# PlacaE3.net
KiCad netlist of a schematic drawn in Altium Designer
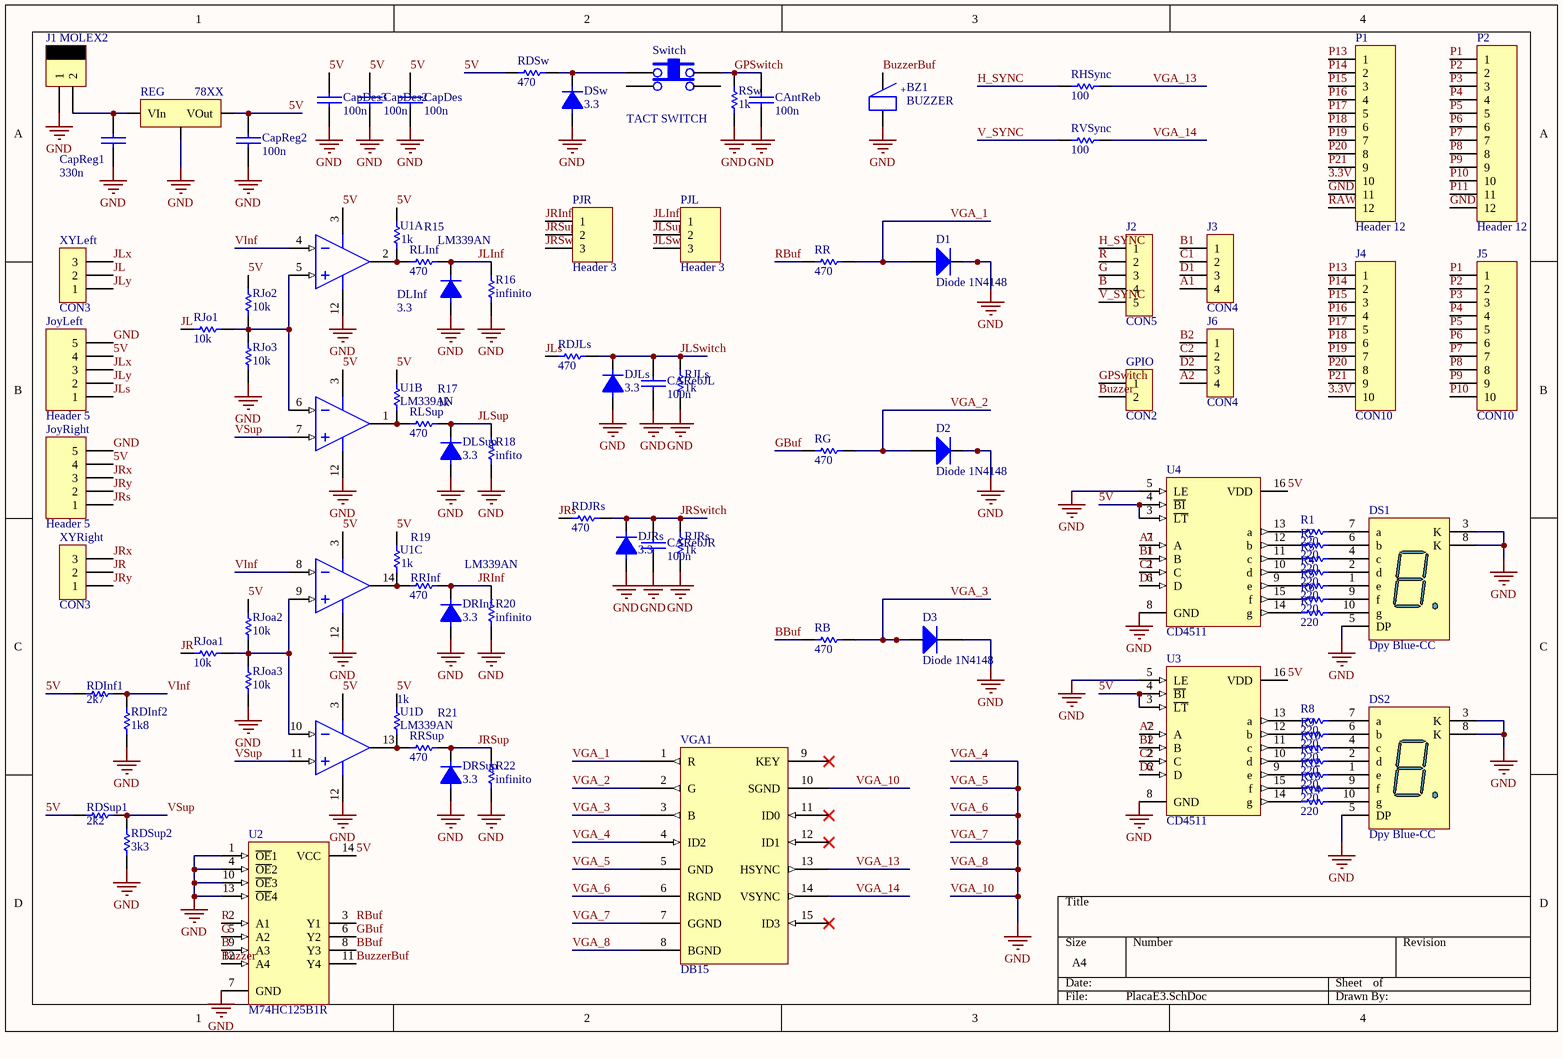
[diagram p0: PlacaE3.SchDoc]

(export (version "E")
  (design (tool "Eeschema 10.0.6"))
  (components
    (comp (ref "BZ1") (value "BUZZER") (footprint "BUZZER 12MM") (libsource (lib "LIBEBAL") (part "BUZZER")))
    (comp (ref "CAntReb") (value "100n") (footprint "CAP200") (libsource (lib "LIBEBAL") (part "CAP")))
    (comp (ref "CapDes") (value "100n") (footprint "CAP200") (libsource (lib "LIBEBAL") (part "CAP")))
    (comp (ref "CapDes2") (value "100n") (footprint "CAP200") (libsource (lib "LIBEBAL") (part "CAP")))
    (comp (ref "CapDes3") (value "100n") (footprint "CAP200") (libsource (lib "LIBEBAL") (part "CAP")))
    (comp (ref "CapReg1") (value "330n") (footprint "CAP200") (libsource (lib "LIBEBAL") (part "CAP")))
    (comp (ref "CapReg2") (value "100n") (footprint "CAP200") (libsource (lib "LIBEBAL") (part "CAP")))
    (comp (ref "CARebJL") (value "100n") (footprint "CAP200") (libsource (lib "LIBEBAL") (part "CAP")))
    (comp (ref "CARebJR") (value "100n") (footprint "CAP200") (libsource (lib "LIBEBAL") (part "CAP")))
    (comp (ref "D1")
      (value "Diode 1N4148")
      (footprint "DO-35")
      (description "High Conductance Fast Diode")
      (fields (field (name "PUBLISHER") "Altium Limited"))
      (libsource (lib "Miscellaneous Devices") (part "Diode 1N4148"))
    )
    (comp (ref "D2")
      (value "Diode 1N4148")
      (footprint "DO-35")
      (description "High Conductance Fast Diode")
      (fields (field (name "PUBLISHER") "Altium Limited"))
      (libsource (lib "Miscellaneous Devices") (part "Diode 1N4148"))
    )
    (comp (ref "D3")
      (value "Diode 1N4148")
      (footprint "DO-35")
      (description "High Conductance Fast Diode")
      (fields (field (name "PUBLISHER") "Altium Limited"))
      (libsource (lib "Miscellaneous Devices") (part "Diode 1N4148"))
    )
    (comp (ref "DJLs") (value "3.3") (footprint "DO41") (libsource (lib "LIBEBAL") (part "DIODO")))
    (comp (ref "DJRs") (value "3.3") (footprint "DO41") (libsource (lib "LIBEBAL") (part "DIODO")))
    (comp (ref "DLInf") (value "3.3") (footprint "DO41") (libsource (lib "LIBEBAL") (part "DIODO")))
    (comp (ref "DLSup") (value "3.3") (footprint "DO41") (libsource (lib "LIBEBAL") (part "DIODO")))
    (comp (ref "DRInf") (value "3.3") (footprint "DO41") (libsource (lib "LIBEBAL") (part "DIODO")))
    (comp (ref "DRSup") (value "3.3") (footprint "DO41") (libsource (lib "LIBEBAL") (part "DIODO")))
    (comp (ref "DS1")
      (value "Dpy Blue-CC")
      (footprint "H")
      (description "14.2 mm General Purpose Blue 7-Segment Display: CC, RH DP, Gray Surface")
      (fields (field (name "PUBLISHER") "Altium Limited"))
      (libsource (lib "Miscellaneous Devices") (part "Dpy Blue-CC"))
    )
    (comp (ref "DS2")
      (value "Dpy Blue-CC")
      (footprint "H")
      (description "14.2 mm General Purpose Blue 7-Segment Display: CC, RH DP, Gray Surface")
      (fields (field (name "PUBLISHER") "Altium Limited"))
      (libsource (lib "Miscellaneous Devices") (part "Dpy Blue-CC"))
    )
    (comp (ref "DSw") (value "3.3") (footprint "DO41") (libsource (lib "LIBEBAL") (part "DIODO")))
    (comp (ref "GPIO") (value "CON2") (footprint "SIP2") (libsource (lib "LIBEBAL") (part "CON2")))
    (comp (ref "J1") (value "MOLEX2") (footprint "MOLEX2") (libsource (lib "LIBEBAL") (part "MOLEX2")))
    (comp (ref "J2") (value "CON5") (footprint "SIP5") (libsource (lib "LIBEBAL") (part "CON5")))
    (comp (ref "J3") (value "CON4") (footprint "SIP4") (libsource (lib "LIBEBAL") (part "CON4")))
    (comp (ref "J4") (value "CON10") (footprint "SIP10") (libsource (lib "LIBEBAL") (part "CON10")))
    (comp (ref "J5") (value "CON10") (footprint "SIP10") (libsource (lib "LIBEBAL") (part "CON10")))
    (comp (ref "J6") (value "CON4") (footprint "SIP4") (libsource (lib "LIBEBAL") (part "CON4")))
    (comp (ref "JoyLeft")
      (value "Header 5")
      (footprint "HDR1X5")
      (description "Header, 5-Pin")
      (fields (field (name "PUBLISHER") "Altium Limited"))
      (libsource (lib "Miscellaneous Connectors") (part "Header 5"))
    )
    (comp (ref "JoyRight")
      (value "Header 5")
      (footprint "HDR1X5")
      (description "Header, 5-Pin")
      (fields (field (name "PUBLISHER") "Altium Limited"))
      (libsource (lib "Miscellaneous Connectors") (part "Header 5"))
    )
    (comp (ref "P1")
      (value "Header 12")
      (footprint "HDR1X12")
      (description "Header, 12-Pin")
      (fields (field (name "PUBLISHER") "Altium Limited"))
      (libsource (lib "Miscellaneous Connectors") (part "Header 12"))
    )
    (comp (ref "P2")
      (value "Header 12")
      (footprint "HDR1X12")
      (description "Header, 12-Pin")
      (fields (field (name "PUBLISHER") "Altium Limited"))
      (libsource (lib "Miscellaneous Connectors") (part "Header 12"))
    )
    (comp (ref "PJL")
      (value "Header 3")
      (footprint "HDR1X3")
      (description "Header, 3-Pin")
      (fields (field (name "PUBLISHER") "Altium Limited"))
      (libsource (lib "Miscellaneous Connectors") (part "Header 3"))
    )
    (comp (ref "PJR")
      (value "Header 3")
      (footprint "HDR1X3")
      (description "Header, 3-Pin")
      (fields (field (name "PUBLISHER") "Altium Limited"))
      (libsource (lib "Miscellaneous Connectors") (part "Header 3"))
    )
    (comp (ref "R1") (value "220") (footprint "0805") (libsource (lib "LIBEBAL") (part "RES")))
    (comp (ref "R2") (value "220") (footprint "0805") (libsource (lib "LIBEBAL") (part "RES")))
    (comp (ref "R3") (value "220") (footprint "0805") (libsource (lib "LIBEBAL") (part "RES")))
    (comp (ref "R4") (value "220") (footprint "0805") (libsource (lib "LIBEBAL") (part "RES")))
    (comp (ref "R5") (value "220") (footprint "0805") (libsource (lib "LIBEBAL") (part "RES")))
    (comp (ref "R6") (value "220") (footprint "0805") (libsource (lib "LIBEBAL") (part "RES")))
    (comp (ref "R7") (value "220") (footprint "0805") (libsource (lib "LIBEBAL") (part "RES")))
    (comp (ref "R8") (value "220") (footprint "0805") (libsource (lib "LIBEBAL") (part "RES")))
    (comp (ref "R9") (value "220") (footprint "0805") (libsource (lib "LIBEBAL") (part "RES")))
    (comp (ref "R10") (value "220") (footprint "0805") (libsource (lib "LIBEBAL") (part "RES")))
    (comp (ref "R11") (value "220") (footprint "0805") (libsource (lib "LIBEBAL") (part "RES")))
    (comp (ref "R12") (value "220") (footprint "0805") (libsource (lib "LIBEBAL") (part "RES")))
    (comp (ref "R13") (value "220") (footprint "0805") (libsource (lib "LIBEBAL") (part "RES")))
    (comp (ref "R14") (value "220") (footprint "0805") (libsource (lib "LIBEBAL") (part "RES")))
    (comp (ref "R15") (value "1k") (footprint "0805") (libsource (lib "LIBEBAL") (part "RES")))
    (comp (ref "R16") (value "infinito") (footprint "0805") (libsource (lib "LIBEBAL") (part "RES")))
    (comp (ref "R17") (value "1k") (footprint "0805") (libsource (lib "LIBEBAL") (part "RES")))
    (comp (ref "R18") (value "infito") (footprint "0805") (libsource (lib "LIBEBAL") (part "RES")))
    (comp (ref "R19") (value "1k") (footprint "0805") (libsource (lib "LIBEBAL") (part "RES")))
    (comp (ref "R20") (value "infinito") (footprint "0805") (libsource (lib "LIBEBAL") (part "RES")))
    (comp (ref "R21") (value "1k") (footprint "0805") (libsource (lib "LIBEBAL") (part "RES")))
    (comp (ref "R22") (value "infinito") (footprint "0805") (libsource (lib "LIBEBAL") (part "RES")))
    (comp (ref "RB") (value "470") (footprint "RES400") (libsource (lib "LIBEBAL") (part "RES")))
    (comp (ref "RDInf1") (value "2k7") (footprint "RES400") (libsource (lib "LIBEBAL") (part "RES")))
    (comp (ref "RDInf2") (value "1k8") (footprint "RES400") (libsource (lib "LIBEBAL") (part "RES")))
    (comp (ref "RDJLs") (value "470") (footprint "RES400") (libsource (lib "LIBEBAL") (part "RES")))
    (comp (ref "RDJRs") (value "470") (footprint "RES400") (libsource (lib "LIBEBAL") (part "RES")))
    (comp (ref "RDSup1") (value "2k2") (footprint "RES400") (libsource (lib "LIBEBAL") (part "RES")))
    (comp (ref "RDSup2") (value "3k3") (footprint "RES400") (libsource (lib "LIBEBAL") (part "RES")))
    (comp (ref "RDSw") (value "470") (footprint "RES400") (libsource (lib "LIBEBAL") (part "RES")))
    (comp (ref "REG")
      (value "78XX")
      (footprint "TO-220 V")
      (description "REGULDOR POSITIVO")
      (libsource (lib "LIBEBAL") (part "78XX"))
    )
    (comp (ref "RG") (value "470") (footprint "RES400") (libsource (lib "LIBEBAL") (part "RES")))
    (comp (ref "RHSync") (value "100") (footprint "RES400") (libsource (lib "LIBEBAL") (part "RES")))
    (comp (ref "RJLs") (value "1k") (footprint "RES400") (libsource (lib "LIBEBAL") (part "RES")))
    (comp (ref "RJo1") (value "10k") (footprint "0805") (libsource (lib "LIBEBAL") (part "RES")))
    (comp (ref "RJo2") (value "10k") (footprint "0805") (libsource (lib "LIBEBAL") (part "RES")))
    (comp (ref "RJo3") (value "10k") (footprint "0805") (libsource (lib "LIBEBAL") (part "RES")))
    (comp (ref "RJoa1") (value "10k") (footprint "0805") (libsource (lib "LIBEBAL") (part "RES")))
    (comp (ref "RJoa2") (value "10k") (footprint "0805") (libsource (lib "LIBEBAL") (part "RES")))
    (comp (ref "RJoa3") (value "10k") (footprint "0805") (libsource (lib "LIBEBAL") (part "RES")))
    (comp (ref "RJRs") (value "1k") (footprint "RES400") (libsource (lib "LIBEBAL") (part "RES")))
    (comp (ref "RLInf") (value "470") (footprint "RES400") (libsource (lib "LIBEBAL") (part "RES")))
    (comp (ref "RLSup") (value "470") (footprint "RES400") (libsource (lib "LIBEBAL") (part "RES")))
    (comp (ref "RR") (value "470") (footprint "RES400") (libsource (lib "LIBEBAL") (part "RES")))
    (comp (ref "RRInf") (value "470") (footprint "RES400") (libsource (lib "LIBEBAL") (part "RES")))
    (comp (ref "RRSup") (value "470") (footprint "RES400") (libsource (lib "LIBEBAL") (part "RES")))
    (comp (ref "RSw") (value "1k") (footprint "RES400") (libsource (lib "LIBEBAL") (part "RES")))
    (comp (ref "RVSync") (value "100") (footprint "RES400") (libsource (lib "LIBEBAL") (part "RES")))
    (comp (ref "Switch")
      (value "TACT SWITCH")
      (footprint "TACTSWITCH")
      (libsource (lib "LIBEBAL") (part "TACT SWITCH"))
    )
    (comp (ref "U1")
      (value "LM339AN")
      (footprint "DIP14")
      (description "Low-Power Quad Voltage Comparator")
      (fields (field (name "PUBLISHER") "Altium Limited"))
      (libsource (lib "ST Analog Comparator") (part "LM339AN"))
    )
    (comp (ref "U2")
      (value "M74HC125B1R")
      (footprint "DIP14")
      (description "Quad Bus Buffer (3-State)")
      (fields (field (name "PUBLISHER") "Altium Limited"))
      (libsource (lib "ST Logic Buffer Line Driver") (part "M74HC125B1R"))
    )
    (comp (ref "U3")
      (value "CD4511")
      (footprint "DIP16")
      (description "BCD to 7 SEGMENTOS")
      (libsource (lib "LIBEBAL") (part "CD4511"))
    )
    (comp (ref "U4")
      (value "CD4511")
      (footprint "DIP16")
      (description "BCD to 7 SEGMENTOS")
      (libsource (lib "LIBEBAL") (part "CD4511"))
    )
    (comp (ref "VGA1")
      (value "DB15")
      (footprint "DB15_DSUB")
      (description "DB15 VGA Male Connector")
      (libsource (lib "VGA_CON") (part "DB15"))
    )
    (comp (ref "XYLeft") (value "CON3") (footprint "SIP3") (libsource (lib "LIBEBAL") (part "CON3")))
    (comp (ref "XYRight") (value "CON3") (footprint "SIP3") (libsource (lib "LIBEBAL") (part "CON3")))
  )
  (nets
    (net (code "1") (name "/3.3V") (class "Default")
      (node (ref "J4") (pin "10") (pinfunction "10_10") (pintype "passive"))
      (node (ref "P1") (pin "10") (pinfunction "10_10") (pintype "passive"))
    )
    (net (code "2") (name "/5V") (class "Default")
      (node (ref "CapDes") (pin "1") (pinfunction "1_1") (pintype "passive"))
      (node (ref "CapDes2") (pin "1") (pinfunction "1_1") (pintype "passive"))
      (node (ref "CapDes3") (pin "1") (pinfunction "1_1") (pintype "passive"))
      (node (ref "CapReg2") (pin "1") (pinfunction "1_1") (pintype "passive"))
      (node (ref "JoyLeft") (pin "4") (pinfunction "4_4") (pintype "passive"))
      (node (ref "JoyRight") (pin "4") (pinfunction "4_4") (pintype "passive"))
      (node (ref "R15") (pin "2") (pinfunction "2_2") (pintype "passive"))
      (node (ref "R17") (pin "2") (pinfunction "2_2") (pintype "passive"))
      (node (ref "R19") (pin "2") (pinfunction "2_2") (pintype "passive"))
      (node (ref "R21") (pin "2") (pinfunction "2_2") (pintype "passive"))
      (node (ref "RDInf1") (pin "1") (pinfunction "1_1") (pintype "passive"))
      (node (ref "RDSup1") (pin "1") (pinfunction "1_1") (pintype "passive"))
      (node (ref "RDSw") (pin "1") (pinfunction "1_1") (pintype "passive"))
      (node (ref "REG") (pin "3") (pinfunction "VOut_3") (pintype "passive"))
      (node (ref "RJo2") (pin "2") (pinfunction "2_2") (pintype "passive"))
      (node (ref "RJoa2") (pin "2") (pinfunction "2_2") (pintype "passive"))
      (node (ref "U1") (pin "3") (pinfunction "V+_3") (pintype "power_in"))
      (node (ref "U2") (pin "14") (pinfunction "VCC_14") (pintype "power_in"))
      (node (ref "U3") (pin "16") (pinfunction "VDD_16") (pintype "power_in"))
      (node (ref "U3") (pin "3") (pinfunction "~{LT}_3") (pintype "input"))
      (node (ref "U3") (pin "4") (pinfunction "~{BI}_4") (pintype "input"))
      (node (ref "U4") (pin "16") (pinfunction "VDD_16") (pintype "power_in"))
      (node (ref "U4") (pin "3") (pinfunction "~{LT}_3") (pintype "input"))
      (node (ref "U4") (pin "4") (pinfunction "~{BI}_4") (pintype "input"))
    )
    (net (code "3") (name "/A1") (class "Default")
      (node (ref "J3") (pin "4") (pinfunction "4_4") (pintype "passive"))
      (node (ref "U4") (pin "7") (pinfunction "A_7") (pintype "input"))
    )
    (net (code "4") (name "/A2") (class "Default")
      (node (ref "J6") (pin "4") (pinfunction "4_4") (pintype "passive"))
      (node (ref "U3") (pin "7") (pinfunction "A_7") (pintype "input"))
    )
    (net (code "5") (name "/B") (class "Default")
      (node (ref "J2") (pin "4") (pinfunction "4_4") (pintype "passive"))
      (node (ref "U2") (pin "9") (pinfunction "A3_9") (pintype "input"))
    )
    (net (code "6") (name "/B1") (class "Default")
      (node (ref "J3") (pin "1") (pinfunction "1_1") (pintype "passive"))
      (node (ref "U4") (pin "1") (pinfunction "B_1") (pintype "input"))
    )
    (net (code "7") (name "/B2") (class "Default")
      (node (ref "J6") (pin "1") (pinfunction "1_1") (pintype "passive"))
      (node (ref "U3") (pin "1") (pinfunction "B_1") (pintype "input"))
    )
    (net (code "8") (name "/BBuf") (class "Default")
      (node (ref "RB") (pin "1") (pinfunction "1_1") (pintype "passive"))
      (node (ref "U2") (pin "8") (pinfunction "Y3_8") (pintype "tri_state"))
    )
    (net (code "9") (name "/Buzzer") (class "Default")
      (node (ref "GPIO") (pin "2") (pinfunction "2_2") (pintype "passive"))
      (node (ref "U2") (pin "12") (pinfunction "A4_12") (pintype "input"))
    )
    (net (code "10") (name "/BuzzerBuf") (class "Default")
      (node (ref "BZ1") (pin "1") (pinfunction "1_1") (pintype "passive"))
      (node (ref "U2") (pin "11") (pinfunction "Y4_11") (pintype "tri_state"))
    )
    (net (code "11") (name "/C1") (class "Default")
      (node (ref "J3") (pin "2") (pinfunction "2_2") (pintype "passive"))
      (node (ref "U4") (pin "2") (pinfunction "C_2") (pintype "input"))
    )
    (net (code "12") (name "/C2") (class "Default")
      (node (ref "J6") (pin "2") (pinfunction "2_2") (pintype "passive"))
      (node (ref "U3") (pin "2") (pinfunction "C_2") (pintype "input"))
    )
    (net (code "13") (name "/D1") (class "Default")
      (node (ref "J3") (pin "3") (pinfunction "3_3") (pintype "passive"))
      (node (ref "U4") (pin "6") (pinfunction "D_6") (pintype "input"))
    )
    (net (code "14") (name "/D2") (class "Default")
      (node (ref "J6") (pin "3") (pinfunction "3_3") (pintype "passive"))
      (node (ref "U3") (pin "6") (pinfunction "D_6") (pintype "input"))
    )
    (net (code "15") (name "/G") (class "Default")
      (node (ref "J2") (pin "3") (pinfunction "3_3") (pintype "passive"))
      (node (ref "U2") (pin "5") (pinfunction "A2_5") (pintype "input"))
    )
    (net (code "16") (name "/GBuf") (class "Default")
      (node (ref "RG") (pin "1") (pinfunction "1_1") (pintype "passive"))
      (node (ref "U2") (pin "6") (pinfunction "Y2_6") (pintype "tri_state"))
    )
    (net (code "17") (name "/GPSwitch") (class "Default")
      (node (ref "CAntReb") (pin "1") (pinfunction "1_1") (pintype "passive"))
      (node (ref "GPIO") (pin "1") (pinfunction "1_1") (pintype "passive"))
      (node (ref "RSw") (pin "2") (pinfunction "2_2") (pintype "passive"))
      (node (ref "Switch") (pin "3") (pinfunction "3_3") (pintype "passive"))
    )
    (net (code "18") (name "/H_SYNC") (class "Default")
      (node (ref "J2") (pin "1") (pinfunction "1_1") (pintype "passive"))
      (node (ref "RHSync") (pin "1") (pinfunction "1_1") (pintype "passive"))
    )
    (net (code "19") (name "/JL") (class "Default")
      (node (ref "RJo1") (pin "1") (pinfunction "1_1") (pintype "passive"))
      (node (ref "XYLeft") (pin "2") (pinfunction "2_2") (pintype "passive"))
    )
    (net (code "20") (name "/JLInf") (class "Default")
      (node (ref "DLInf") (pin "2") (pinfunction "2_2") (pintype "passive"))
      (node (ref "PJL") (pin "1") (pinfunction "1_1") (pintype "passive"))
      (node (ref "R16") (pin "2") (pinfunction "2_2") (pintype "passive"))
      (node (ref "RLInf") (pin "2") (pinfunction "2_2") (pintype "passive"))
    )
    (net (code "21") (name "/JLSup") (class "Default")
      (node (ref "DLSup") (pin "2") (pinfunction "2_2") (pintype "passive"))
      (node (ref "PJL") (pin "2") (pinfunction "2_2") (pintype "passive"))
      (node (ref "R18") (pin "2") (pinfunction "2_2") (pintype "passive"))
      (node (ref "RLSup") (pin "2") (pinfunction "2_2") (pintype "passive"))
    )
    (net (code "22") (name "/JLSwitch") (class "Default")
      (node (ref "CARebJL") (pin "1") (pinfunction "1_1") (pintype "passive"))
      (node (ref "DJLs") (pin "2") (pinfunction "2_2") (pintype "passive"))
      (node (ref "PJL") (pin "3") (pinfunction "3_3") (pintype "passive"))
      (node (ref "RDJLs") (pin "2") (pinfunction "2_2") (pintype "passive"))
      (node (ref "RJLs") (pin "2") (pinfunction "2_2") (pintype "passive"))
    )
    (net (code "23") (name "/JLs") (class "Default")
      (node (ref "JoyLeft") (pin "1") (pinfunction "1_1") (pintype "passive"))
      (node (ref "RDJLs") (pin "1") (pinfunction "1_1") (pintype "passive"))
    )
    (net (code "24") (name "/JLx") (class "Default")
      (node (ref "JoyLeft") (pin "3") (pinfunction "3_3") (pintype "passive"))
      (node (ref "XYLeft") (pin "3") (pinfunction "3_3") (pintype "passive"))
    )
    (net (code "25") (name "/JLy") (class "Default")
      (node (ref "JoyLeft") (pin "2") (pinfunction "2_2") (pintype "passive"))
      (node (ref "XYLeft") (pin "1") (pinfunction "1_1") (pintype "passive"))
    )
    (net (code "26") (name "/JR") (class "Default")
      (node (ref "RJoa1") (pin "1") (pinfunction "1_1") (pintype "passive"))
      (node (ref "XYRight") (pin "2") (pinfunction "2_2") (pintype "passive"))
    )
    (net (code "27") (name "/JRInf") (class "Default")
      (node (ref "DRInf") (pin "2") (pinfunction "2_2") (pintype "passive"))
      (node (ref "PJR") (pin "1") (pinfunction "1_1") (pintype "passive"))
      (node (ref "R20") (pin "2") (pinfunction "2_2") (pintype "passive"))
      (node (ref "RRInf") (pin "2") (pinfunction "2_2") (pintype "passive"))
    )
    (net (code "28") (name "/JRSup") (class "Default")
      (node (ref "DRSup") (pin "2") (pinfunction "2_2") (pintype "passive"))
      (node (ref "PJR") (pin "2") (pinfunction "2_2") (pintype "passive"))
      (node (ref "R22") (pin "2") (pinfunction "2_2") (pintype "passive"))
      (node (ref "RRSup") (pin "2") (pinfunction "2_2") (pintype "passive"))
    )
    (net (code "29") (name "/JRSwitch") (class "Default")
      (node (ref "CARebJR") (pin "1") (pinfunction "1_1") (pintype "passive"))
      (node (ref "DJRs") (pin "2") (pinfunction "2_2") (pintype "passive"))
      (node (ref "PJR") (pin "3") (pinfunction "3_3") (pintype "passive"))
      (node (ref "RDJRs") (pin "2") (pinfunction "2_2") (pintype "passive"))
      (node (ref "RJRs") (pin "2") (pinfunction "2_2") (pintype "passive"))
    )
    (net (code "30") (name "/JRs") (class "Default")
      (node (ref "JoyRight") (pin "1") (pinfunction "1_1") (pintype "passive"))
      (node (ref "RDJRs") (pin "1") (pinfunction "1_1") (pintype "passive"))
    )
    (net (code "31") (name "/JRx") (class "Default")
      (node (ref "JoyRight") (pin "3") (pinfunction "3_3") (pintype "passive"))
      (node (ref "XYRight") (pin "3") (pinfunction "3_3") (pintype "passive"))
    )
    (net (code "32") (name "/JRy") (class "Default")
      (node (ref "JoyRight") (pin "2") (pinfunction "2_2") (pintype "passive"))
      (node (ref "XYRight") (pin "1") (pinfunction "1_1") (pintype "passive"))
    )
    (net (code "33") (name "/P1") (class "Default")
      (node (ref "J5") (pin "1") (pinfunction "1_1") (pintype "passive"))
      (node (ref "P2") (pin "1") (pinfunction "1_1") (pintype "passive"))
    )
    (net (code "34") (name "/P2") (class "Default")
      (node (ref "J5") (pin "2") (pinfunction "2_2") (pintype "passive"))
      (node (ref "P2") (pin "2") (pinfunction "2_2") (pintype "passive"))
    )
    (net (code "35") (name "/P3") (class "Default")
      (node (ref "J5") (pin "3") (pinfunction "3_3") (pintype "passive"))
      (node (ref "P2") (pin "3") (pinfunction "3_3") (pintype "passive"))
    )
    (net (code "36") (name "/P4") (class "Default")
      (node (ref "J5") (pin "4") (pinfunction "4_4") (pintype "passive"))
      (node (ref "P2") (pin "4") (pinfunction "4_4") (pintype "passive"))
    )
    (net (code "37") (name "/P5") (class "Default")
      (node (ref "J5") (pin "5") (pinfunction "5_5") (pintype "passive"))
      (node (ref "P2") (pin "5") (pinfunction "5_5") (pintype "passive"))
    )
    (net (code "38") (name "/P6") (class "Default")
      (node (ref "J5") (pin "6") (pinfunction "6_6") (pintype "passive"))
      (node (ref "P2") (pin "6") (pinfunction "6_6") (pintype "passive"))
    )
    (net (code "39") (name "/P7") (class "Default")
      (node (ref "J5") (pin "7") (pinfunction "7_7") (pintype "passive"))
      (node (ref "P2") (pin "7") (pinfunction "7_7") (pintype "passive"))
    )
    (net (code "40") (name "/P8") (class "Default")
      (node (ref "J5") (pin "8") (pinfunction "8_8") (pintype "passive"))
      (node (ref "P2") (pin "8") (pinfunction "8_8") (pintype "passive"))
    )
    (net (code "41") (name "/P9") (class "Default")
      (node (ref "J5") (pin "9") (pinfunction "9_9") (pintype "passive"))
      (node (ref "P2") (pin "9") (pinfunction "9_9") (pintype "passive"))
    )
    (net (code "42") (name "/P10") (class "Default")
      (node (ref "J5") (pin "10") (pinfunction "10_10") (pintype "passive"))
      (node (ref "P2") (pin "10") (pinfunction "10_10") (pintype "passive"))
    )
    (net (code "43") (name "/P11") (class "Default")
      (node (ref "P2") (pin "11") (pinfunction "11_11") (pintype "passive"))
    )
    (net (code "44") (name "/P13") (class "Default")
      (node (ref "J4") (pin "1") (pinfunction "1_1") (pintype "passive"))
      (node (ref "P1") (pin "1") (pinfunction "1_1") (pintype "passive"))
    )
    (net (code "45") (name "/P14") (class "Default")
      (node (ref "J4") (pin "2") (pinfunction "2_2") (pintype "passive"))
      (node (ref "P1") (pin "2") (pinfunction "2_2") (pintype "passive"))
    )
    (net (code "46") (name "/P15") (class "Default")
      (node (ref "J4") (pin "3") (pinfunction "3_3") (pintype "passive"))
      (node (ref "P1") (pin "3") (pinfunction "3_3") (pintype "passive"))
    )
    (net (code "47") (name "/P16") (class "Default")
      (node (ref "J4") (pin "4") (pinfunction "4_4") (pintype "passive"))
      (node (ref "P1") (pin "4") (pinfunction "4_4") (pintype "passive"))
    )
    (net (code "48") (name "/P17") (class "Default")
      (node (ref "J4") (pin "5") (pinfunction "5_5") (pintype "passive"))
      (node (ref "P1") (pin "5") (pinfunction "5_5") (pintype "passive"))
    )
    (net (code "49") (name "/P18") (class "Default")
      (node (ref "J4") (pin "6") (pinfunction "6_6") (pintype "passive"))
      (node (ref "P1") (pin "6") (pinfunction "6_6") (pintype "passive"))
    )
    (net (code "50") (name "/P19") (class "Default")
      (node (ref "J4") (pin "7") (pinfunction "7_7") (pintype "passive"))
      (node (ref "P1") (pin "7") (pinfunction "7_7") (pintype "passive"))
    )
    (net (code "51") (name "/P20") (class "Default")
      (node (ref "J4") (pin "8") (pinfunction "8_8") (pintype "passive"))
      (node (ref "P1") (pin "8") (pinfunction "8_8") (pintype "passive"))
    )
    (net (code "52") (name "/P21") (class "Default")
      (node (ref "J4") (pin "9") (pinfunction "9_9") (pintype "passive"))
      (node (ref "P1") (pin "9") (pinfunction "9_9") (pintype "passive"))
    )
    (net (code "53") (name "/R") (class "Default")
      (node (ref "J2") (pin "2") (pinfunction "2_2") (pintype "passive"))
      (node (ref "U2") (pin "2") (pinfunction "A1_2") (pintype "input"))
    )
    (net (code "54") (name "/RAW") (class "Default")
      (node (ref "P1") (pin "12") (pinfunction "12_12") (pintype "passive"))
    )
    (net (code "55") (name "/RBuf") (class "Default")
      (node (ref "RR") (pin "1") (pinfunction "1_1") (pintype "passive"))
      (node (ref "U2") (pin "3") (pinfunction "Y1_3") (pintype "tri_state"))
    )
    (net (code "56") (name "/VGA_1") (class "Default")
      (node (ref "D1") (pin "1") (pinfunction "A_1") (pintype "passive"))
      (node (ref "RR") (pin "2") (pinfunction "2_2") (pintype "passive"))
      (node (ref "VGA1") (pin "1") (pinfunction "R_1") (pintype "output"))
    )
    (net (code "57") (name "/VGA_2") (class "Default")
      (node (ref "D2") (pin "1") (pinfunction "A_1") (pintype "passive"))
      (node (ref "RG") (pin "2") (pinfunction "2_2") (pintype "passive"))
      (node (ref "VGA1") (pin "2") (pinfunction "G_2") (pintype "output"))
    )
    (net (code "58") (name "/VGA_3") (class "Default")
      (node (ref "D3") (pin "1") (pinfunction "A_1") (pintype "passive"))
      (node (ref "RB") (pin "2") (pinfunction "2_2") (pintype "passive"))
      (node (ref "VGA1") (pin "3") (pinfunction "B_3") (pintype "output"))
    )
    (net (code "59") (name "/VGA_13") (class "Default")
      (node (ref "RHSync") (pin "2") (pinfunction "2_2") (pintype "passive"))
      (node (ref "VGA1") (pin "13") (pinfunction "HSYNC_13") (pintype "output"))
    )
    (net (code "60") (name "/VGA_14") (class "Default")
      (node (ref "RVSync") (pin "2") (pinfunction "2_2") (pintype "passive"))
      (node (ref "VGA1") (pin "14") (pinfunction "VSYNC_14") (pintype "output"))
    )
    (net (code "61") (name "/VInf") (class "Default")
      (node (ref "RDInf1") (pin "2") (pinfunction "2_2") (pintype "passive"))
      (node (ref "RDInf2") (pin "2") (pinfunction "2_2") (pintype "passive"))
      (node (ref "U1") (pin "4") (pinfunction "IN-_4") (pintype "input"))
      (node (ref "U1") (pin "8") (pinfunction "IN-_8") (pintype "input"))
    )
    (net (code "62") (name "/VSup") (class "Default")
      (node (ref "RDSup1") (pin "2") (pinfunction "2_2") (pintype "passive"))
      (node (ref "RDSup2") (pin "2") (pinfunction "2_2") (pintype "passive"))
      (node (ref "U1") (pin "11") (pinfunction "IN+_11") (pintype "input"))
      (node (ref "U1") (pin "7") (pinfunction "IN+_7") (pintype "input"))
    )
    (net (code "63") (name "/V_SYNC") (class "Default")
      (node (ref "J2") (pin "5") (pinfunction "5_5") (pintype "passive"))
      (node (ref "RVSync") (pin "1") (pinfunction "1_1") (pintype "passive"))
    )
    (net (code "64") (name "GND") (class "Default")
      (node (ref "BZ1") (pin "2") (pinfunction "2_2") (pintype "passive"))
      (node (ref "CARebJL") (pin "2") (pinfunction "2_2") (pintype "passive"))
      (node (ref "CARebJR") (pin "2") (pinfunction "2_2") (pintype "passive"))
      (node (ref "CAntReb") (pin "2") (pinfunction "2_2") (pintype "passive"))
      (node (ref "CapDes") (pin "2") (pinfunction "2_2") (pintype "passive"))
      (node (ref "CapDes2") (pin "2") (pinfunction "2_2") (pintype "passive"))
      (node (ref "CapDes3") (pin "2") (pinfunction "2_2") (pintype "passive"))
      (node (ref "CapReg1") (pin "2") (pinfunction "2_2") (pintype "passive"))
      (node (ref "CapReg2") (pin "2") (pinfunction "2_2") (pintype "passive"))
      (node (ref "D1") (pin "2") (pinfunction "K_2") (pintype "passive"))
      (node (ref "D2") (pin "2") (pinfunction "K_2") (pintype "passive"))
      (node (ref "D3") (pin "2") (pinfunction "K_2") (pintype "passive"))
      (node (ref "DJLs") (pin "1") (pinfunction "1_1") (pintype "passive"))
      (node (ref "DJRs") (pin "1") (pinfunction "1_1") (pintype "passive"))
      (node (ref "DLInf") (pin "1") (pinfunction "1_1") (pintype "passive"))
      (node (ref "DLSup") (pin "1") (pinfunction "1_1") (pintype "passive"))
      (node (ref "DRInf") (pin "1") (pinfunction "1_1") (pintype "passive"))
      (node (ref "DRSup") (pin "1") (pinfunction "1_1") (pintype "passive"))
      (node (ref "DS1") (pin "3") (pinfunction "K_3") (pintype "passive"))
      (node (ref "DS1") (pin "5") (pinfunction "DP_5") (pintype "passive"))
      (node (ref "DS1") (pin "8") (pinfunction "K_8") (pintype "passive"))
      (node (ref "DS2") (pin "3") (pinfunction "K_3") (pintype "passive"))
      (node (ref "DS2") (pin "5") (pinfunction "DP_5") (pintype "passive"))
      (node (ref "DS2") (pin "8") (pinfunction "K_8") (pintype "passive"))
      (node (ref "DSw") (pin "1") (pinfunction "1_1") (pintype "passive"))
      (node (ref "J1") (pin "1") (pinfunction "1_1") (pintype "passive"))
      (node (ref "JoyLeft") (pin "5") (pinfunction "5_5") (pintype "passive"))
      (node (ref "JoyRight") (pin "5") (pinfunction "5_5") (pintype "passive"))
      (node (ref "P1") (pin "11") (pinfunction "11_11") (pintype "passive"))
      (node (ref "P2") (pin "12") (pinfunction "12_12") (pintype "passive"))
      (node (ref "R16") (pin "1") (pinfunction "1_1") (pintype "passive"))
      (node (ref "R18") (pin "1") (pinfunction "1_1") (pintype "passive"))
      (node (ref "R20") (pin "1") (pinfunction "1_1") (pintype "passive"))
      (node (ref "R22") (pin "1") (pinfunction "1_1") (pintype "passive"))
      (node (ref "RDInf2") (pin "1") (pinfunction "1_1") (pintype "passive"))
      (node (ref "RDSup2") (pin "1") (pinfunction "1_1") (pintype "passive"))
      (node (ref "REG") (pin "2") (pinfunction "GND_2") (pintype "passive"))
      (node (ref "RJLs") (pin "1") (pinfunction "1_1") (pintype "passive"))
      (node (ref "RJRs") (pin "1") (pinfunction "1_1") (pintype "passive"))
      (node (ref "RJo3") (pin "1") (pinfunction "1_1") (pintype "passive"))
      (node (ref "RJoa3") (pin "1") (pinfunction "1_1") (pintype "passive"))
      (node (ref "RSw") (pin "1") (pinfunction "1_1") (pintype "passive"))
      (node (ref "U1") (pin "12") (pinfunction "V-_12") (pintype "power_in"))
      (node (ref "U2") (pin "1") (pinfunction "~{OE}1_1") (pintype "input"))
      (node (ref "U2") (pin "10") (pinfunction "~{OE}3_10") (pintype "input"))
      (node (ref "U2") (pin "13") (pinfunction "~{OE}4_13") (pintype "input"))
      (node (ref "U2") (pin "4") (pinfunction "~{OE}2_4") (pintype "input"))
      (node (ref "U2") (pin "7") (pinfunction "GND_7") (pintype "power_in"))
      (node (ref "U3") (pin "5") (pinfunction "LE_5") (pintype "input"))
      (node (ref "U3") (pin "8") (pinfunction "GND_8") (pintype "power_in"))
      (node (ref "U4") (pin "5") (pinfunction "LE_5") (pintype "input"))
      (node (ref "U4") (pin "8") (pinfunction "GND_8") (pintype "power_in"))
      (node (ref "VGA1") (pin "10") (pinfunction "SGND_10") (pintype "passive"))
      (node (ref "VGA1") (pin "4") (pinfunction "ID2_4") (pintype "input"))
      (node (ref "VGA1") (pin "5") (pinfunction "GND_5") (pintype "passive"))
      (node (ref "VGA1") (pin "6") (pinfunction "RGND_6") (pintype "passive"))
      (node (ref "VGA1") (pin "7") (pinfunction "GGND_7") (pintype "passive"))
      (node (ref "VGA1") (pin "8") (pinfunction "BGND_8") (pintype "passive"))
    )
    (net (code "65") (name "Net-(DS1-a)") (class "Default")
      (node (ref "DS1") (pin "7") (pinfunction "a_7") (pintype "passive"))
      (node (ref "R1") (pin "2") (pinfunction "2_2") (pintype "passive"))
    )
    (net (code "66") (name "Net-(DS1-b)") (class "Default")
      (node (ref "DS1") (pin "6") (pinfunction "b_6") (pintype "passive"))
      (node (ref "R2") (pin "2") (pinfunction "2_2") (pintype "passive"))
    )
    (net (code "67") (name "Net-(DS1-c)") (class "Default")
      (node (ref "DS1") (pin "4") (pinfunction "c_4") (pintype "passive"))
      (node (ref "R3") (pin "2") (pinfunction "2_2") (pintype "passive"))
    )
    (net (code "68") (name "Net-(DS1-d)") (class "Default")
      (node (ref "DS1") (pin "2") (pinfunction "d_2") (pintype "passive"))
      (node (ref "R4") (pin "2") (pinfunction "2_2") (pintype "passive"))
    )
    (net (code "69") (name "Net-(DS1-e)") (class "Default")
      (node (ref "DS1") (pin "1") (pinfunction "e_1") (pintype "passive"))
      (node (ref "R5") (pin "2") (pinfunction "2_2") (pintype "passive"))
    )
    (net (code "70") (name "Net-(DS1-f)") (class "Default")
      (node (ref "DS1") (pin "9") (pinfunction "f_9") (pintype "passive"))
      (node (ref "R6") (pin "2") (pinfunction "2_2") (pintype "passive"))
    )
    (net (code "71") (name "Net-(DS1-g)") (class "Default")
      (node (ref "DS1") (pin "10") (pinfunction "g_10") (pintype "passive"))
      (node (ref "R7") (pin "2") (pinfunction "2_2") (pintype "passive"))
    )
    (net (code "72") (name "Net-(DS2-a)") (class "Default")
      (node (ref "DS2") (pin "7") (pinfunction "a_7") (pintype "passive"))
      (node (ref "R8") (pin "2") (pinfunction "2_2") (pintype "passive"))
    )
    (net (code "73") (name "Net-(DS2-b)") (class "Default")
      (node (ref "DS2") (pin "6") (pinfunction "b_6") (pintype "passive"))
      (node (ref "R9") (pin "2") (pinfunction "2_2") (pintype "passive"))
    )
    (net (code "74") (name "Net-(DS2-c)") (class "Default")
      (node (ref "DS2") (pin "4") (pinfunction "c_4") (pintype "passive"))
      (node (ref "R10") (pin "2") (pinfunction "2_2") (pintype "passive"))
    )
    (net (code "75") (name "Net-(DS2-d)") (class "Default")
      (node (ref "DS2") (pin "2") (pinfunction "d_2") (pintype "passive"))
      (node (ref "R11") (pin "2") (pinfunction "2_2") (pintype "passive"))
    )
    (net (code "76") (name "Net-(DS2-e)") (class "Default")
      (node (ref "DS2") (pin "1") (pinfunction "e_1") (pintype "passive"))
      (node (ref "R12") (pin "2") (pinfunction "2_2") (pintype "passive"))
    )
    (net (code "77") (name "Net-(DS2-f)") (class "Default")
      (node (ref "DS2") (pin "9") (pinfunction "f_9") (pintype "passive"))
      (node (ref "R13") (pin "2") (pinfunction "2_2") (pintype "passive"))
    )
    (net (code "78") (name "Net-(DS2-g)") (class "Default")
      (node (ref "DS2") (pin "10") (pinfunction "g_10") (pintype "passive"))
      (node (ref "R14") (pin "2") (pinfunction "2_2") (pintype "passive"))
    )
    (net (code "79") (name "Net-(DSw-Pad2)") (class "Default")
      (node (ref "DSw") (pin "2") (pinfunction "2_2") (pintype "passive"))
      (node (ref "RDSw") (pin "2") (pinfunction "2_2") (pintype "passive"))
      (node (ref "Switch") (pin "1") (pinfunction "1_1") (pintype "passive"))
    )
    (net (code "80") (name "Net-(REG-VIn)") (class "Default")
      (node (ref "CapReg1") (pin "1") (pinfunction "1_1") (pintype "passive"))
      (node (ref "J1") (pin "2") (pinfunction "2_2") (pintype "passive"))
      (node (ref "REG") (pin "1") (pinfunction "VIn_1") (pintype "passive"))
    )
    (net (code "81") (name "Net-(U1A-IN+)") (class "Default")
      (node (ref "RJo1") (pin "2") (pinfunction "2_2") (pintype "passive"))
      (node (ref "RJo2") (pin "1") (pinfunction "1_1") (pintype "passive"))
      (node (ref "RJo3") (pin "2") (pinfunction "2_2") (pintype "passive"))
      (node (ref "U1") (pin "5") (pinfunction "IN+_5") (pintype "input"))
      (node (ref "U1") (pin "6") (pinfunction "IN-_6") (pintype "input"))
    )
    (net (code "82") (name "Net-(U1A-OUT)") (class "Default")
      (node (ref "R15") (pin "1") (pinfunction "1_1") (pintype "passive"))
      (node (ref "RLInf") (pin "1") (pinfunction "1_1") (pintype "passive"))
      (node (ref "U1") (pin "2") (pinfunction "OUT_2") (pintype "open_collector"))
    )
    (net (code "83") (name "Net-(U1B-OUT)") (class "Default")
      (node (ref "R17") (pin "1") (pinfunction "1_1") (pintype "passive"))
      (node (ref "RLSup") (pin "1") (pinfunction "1_1") (pintype "passive"))
      (node (ref "U1") (pin "1") (pinfunction "OUT_1") (pintype "open_collector"))
    )
    (net (code "84") (name "Net-(U1C-IN+)") (class "Default")
      (node (ref "RJoa1") (pin "2") (pinfunction "2_2") (pintype "passive"))
      (node (ref "RJoa2") (pin "1") (pinfunction "1_1") (pintype "passive"))
      (node (ref "RJoa3") (pin "2") (pinfunction "2_2") (pintype "passive"))
      (node (ref "U1") (pin "10") (pinfunction "IN-_10") (pintype "input"))
      (node (ref "U1") (pin "9") (pinfunction "IN+_9") (pintype "input"))
    )
    (net (code "85") (name "Net-(U1C-OUT)") (class "Default")
      (node (ref "R19") (pin "1") (pinfunction "1_1") (pintype "passive"))
      (node (ref "RRInf") (pin "1") (pinfunction "1_1") (pintype "passive"))
      (node (ref "U1") (pin "14") (pinfunction "OUT_14") (pintype "open_collector"))
    )
    (net (code "86") (name "Net-(U1D-OUT)") (class "Default")
      (node (ref "R21") (pin "1") (pinfunction "1_1") (pintype "passive"))
      (node (ref "RRSup") (pin "1") (pinfunction "1_1") (pintype "passive"))
      (node (ref "U1") (pin "13") (pinfunction "OUT_13") (pintype "open_collector"))
    )
    (net (code "87") (name "Net-(U3-a)") (class "Default")
      (node (ref "R8") (pin "1") (pinfunction "1_1") (pintype "passive"))
      (node (ref "U3") (pin "13") (pinfunction "a_13") (pintype "output"))
    )
    (net (code "88") (name "Net-(U3-b)") (class "Default")
      (node (ref "R9") (pin "1") (pinfunction "1_1") (pintype "passive"))
      (node (ref "U3") (pin "12") (pinfunction "b_12") (pintype "output"))
    )
    (net (code "89") (name "Net-(U3-c)") (class "Default")
      (node (ref "R10") (pin "1") (pinfunction "1_1") (pintype "passive"))
      (node (ref "U3") (pin "11") (pinfunction "c_11") (pintype "output"))
    )
    (net (code "90") (name "Net-(U3-d)") (class "Default")
      (node (ref "R11") (pin "1") (pinfunction "1_1") (pintype "passive"))
      (node (ref "U3") (pin "10") (pinfunction "d_10") (pintype "output"))
    )
    (net (code "91") (name "Net-(U3-e)") (class "Default")
      (node (ref "R12") (pin "1") (pinfunction "1_1") (pintype "passive"))
      (node (ref "U3") (pin "9") (pinfunction "e_9") (pintype "output"))
    )
    (net (code "92") (name "Net-(U3-f)") (class "Default")
      (node (ref "R13") (pin "1") (pinfunction "1_1") (pintype "passive"))
      (node (ref "U3") (pin "15") (pinfunction "f_15") (pintype "output"))
    )
    (net (code "93") (name "Net-(U3-g)") (class "Default")
      (node (ref "R14") (pin "1") (pinfunction "1_1") (pintype "passive"))
      (node (ref "U3") (pin "14") (pinfunction "g_14") (pintype "output"))
    )
    (net (code "94") (name "Net-(U4-a)") (class "Default")
      (node (ref "R1") (pin "1") (pinfunction "1_1") (pintype "passive"))
      (node (ref "U4") (pin "13") (pinfunction "a_13") (pintype "output"))
    )
    (net (code "95") (name "Net-(U4-b)") (class "Default")
      (node (ref "R2") (pin "1") (pinfunction "1_1") (pintype "passive"))
      (node (ref "U4") (pin "12") (pinfunction "b_12") (pintype "output"))
    )
    (net (code "96") (name "Net-(U4-c)") (class "Default")
      (node (ref "R3") (pin "1") (pinfunction "1_1") (pintype "passive"))
      (node (ref "U4") (pin "11") (pinfunction "c_11") (pintype "output"))
    )
    (net (code "97") (name "Net-(U4-d)") (class "Default")
      (node (ref "R4") (pin "1") (pinfunction "1_1") (pintype "passive"))
      (node (ref "U4") (pin "10") (pinfunction "d_10") (pintype "output"))
    )
    (net (code "98") (name "Net-(U4-e)") (class "Default")
      (node (ref "R5") (pin "1") (pinfunction "1_1") (pintype "passive"))
      (node (ref "U4") (pin "9") (pinfunction "e_9") (pintype "output"))
    )
    (net (code "99") (name "Net-(U4-f)") (class "Default")
      (node (ref "R6") (pin "1") (pinfunction "1_1") (pintype "passive"))
      (node (ref "U4") (pin "15") (pinfunction "f_15") (pintype "output"))
    )
    (net (code "100") (name "Net-(U4-g)") (class "Default")
      (node (ref "R7") (pin "1") (pinfunction "1_1") (pintype "passive"))
      (node (ref "U4") (pin "14") (pinfunction "g_14") (pintype "output"))
    )
    (net (code "101") (name "unconnected-(Switch-Pad2)") (class "Default")
      (node (ref "Switch") (pin "2") (pinfunction "2_2") (pintype "passive"))
    )
    (net (code "102") (name "unconnected-(Switch-Pad4)") (class "Default")
      (node (ref "Switch") (pin "4") (pinfunction "4_4") (pintype "passive"))
    )
    (net (code "103") (name "unconnected-(VGA1-ID0-Pad11)") (class "Default")
      (node (ref "VGA1") (pin "11") (pinfunction "ID0_11") (pintype "input+no_connect"))
    )
    (net (code "104") (name "unconnected-(VGA1-ID1-Pad12)") (class "Default")
      (node (ref "VGA1") (pin "12") (pinfunction "ID1_12") (pintype "input+no_connect"))
    )
    (net (code "105") (name "unconnected-(VGA1-ID3-Pad15)") (class "Default")
      (node (ref "VGA1") (pin "15") (pinfunction "ID3_15") (pintype "input+no_connect"))
    )
    (net (code "106") (name "unconnected-(VGA1-KEY-Pad9)") (class "Default")
      (node (ref "VGA1") (pin "9") (pinfunction "KEY_9") (pintype "passive+no_connect"))
    )
  )
)
